# design.net
KiCad netlist of a schematic drawn in Altium Designer
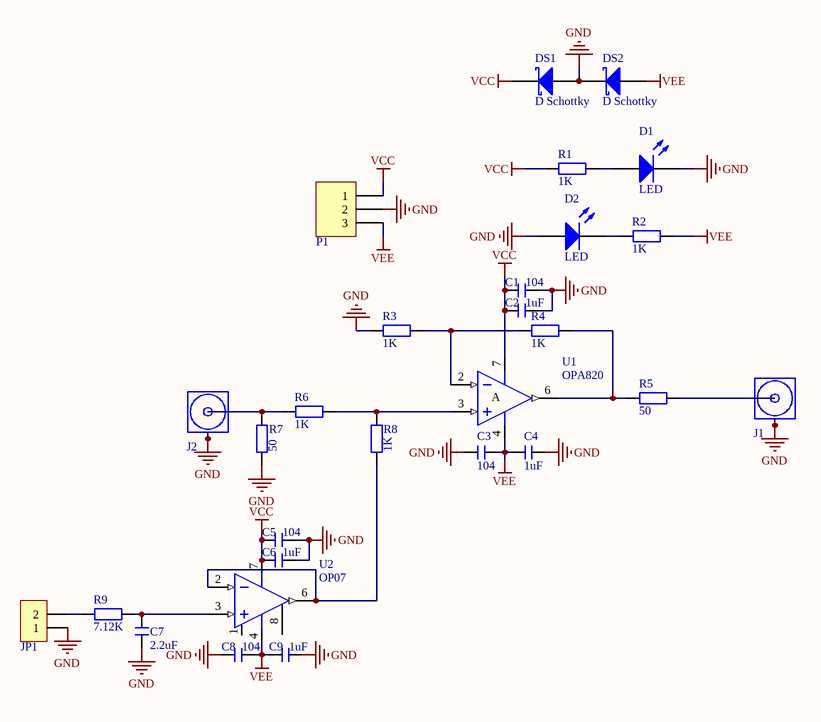
[diagram p0: 同向调偏放大器.SchDoc]

(export (version "E")
  (design (tool "Eeschema 10.0.6"))
  (components
    (comp (ref "C1")
      (value "104")
      (footprint "C 0603")
      (description "无极性贴片电容")
      (fields (field (name "版权归属") "源创客"))
      (libsource (lib "电阻-电容-电感") (part "C"))
    )
    (comp (ref "C2")
      (value "1uF")
      (footprint "C 0603")
      (description "无极性贴片电容")
      (fields (field (name "版权归属") "源创客"))
      (libsource (lib "电阻-电容-电感") (part "C"))
    )
    (comp (ref "C3")
      (value "104")
      (footprint "C 0603")
      (description "无极性贴片电容")
      (fields (field (name "版权归属") "源创客"))
      (libsource (lib "电阻-电容-电感") (part "C"))
    )
    (comp (ref "C4")
      (value "1uF")
      (footprint "C 0603")
      (description "无极性贴片电容")
      (fields (field (name "版权归属") "源创客"))
      (libsource (lib "电阻-电容-电感") (part "C"))
    )
    (comp (ref "C5")
      (value "104")
      (footprint "C 0603")
      (description "无极性贴片电容")
      (fields (field (name "版权归属") "源创客"))
      (libsource (lib "电阻-电容-电感") (part "C"))
    )
    (comp (ref "C6")
      (value "1uF")
      (footprint "C 0603")
      (description "无极性贴片电容")
      (fields (field (name "版权归属") "源创客"))
      (libsource (lib "电阻-电容-电感") (part "C"))
    )
    (comp (ref "C7")
      (value "2.2uF")
      (footprint "C 0603")
      (description "无极性贴片电容")
      (fields (field (name "版权归属") "源创客"))
      (libsource (lib "电阻-电容-电感") (part "C"))
    )
    (comp (ref "C8")
      (value "104")
      (footprint "C 0603")
      (description "无极性贴片电容")
      (fields (field (name "版权归属") "源创客"))
      (libsource (lib "电阻-电容-电感") (part "C"))
    )
    (comp (ref "C9")
      (value "1uF")
      (footprint "C 0603")
      (description "无极性贴片电容")
      (fields (field (name "版权归属") "源创客"))
      (libsource (lib "电阻-电容-电感") (part "C"))
    )
    (comp (ref "D1")
      (value "LED")
      (footprint "LED_0805")
      (description "发光二极管")
      (fields (field (name "PUBLISHER") "Altium Limited"))
      (libsource (lib "LIB") (part "LED"))
    )
    (comp (ref "D2")
      (value "LED")
      (footprint "LED_0805")
      (description "发光二极管")
      (fields (field (name "PUBLISHER") "Altium Limited"))
      (libsource (lib "LIB") (part "LED"))
    )
    (comp (ref "DS1")
      (value "D Schottky")
      (footprint "DIODE-SMA")
      (description "Schottky Diode")
      (fields (field (name "PUBLISHER") "Altium Limited"))
      (libsource (lib "LIB") (part "D Schottky"))
    )
    (comp (ref "DS2")
      (value "D Schottky")
      (footprint "DIODE-SMA")
      (description "Schottky Diode")
      (fields (field (name "PUBLISHER") "Altium Limited"))
      (libsource (lib "LIB") (part "D Schottky"))
    )
    (comp (ref "J1") (value "COAX") (footprint "MCX5.08-5-H") (libsource (lib "LIB") (part "COAX")))
    (comp (ref "J2") (value "COAX") (footprint "MCX5.08-5-H") (libsource (lib "LIB") (part "COAX")))
    (comp (ref "JP1")
      (value "HDR-1X2")
      (footprint "HDR-1X2")
      (description "2P接插件")
      (fields (field (name "版权归属") "源创客"))
      (libsource (lib "接插件") (part "Header 2"))
    )
    (comp (ref "P1")
      (value "Header 3")
      (footprint "HDR3X1_B2")
      (description "接插件")
      (fields (field (name "PUBLISHER") "Altium Limited"))
      (libsource (lib "LIB") (part "Header 3"))
    )
    (comp (ref "R1")
      (value "1K")
      (footprint "R 0805")
      (description "贴片电阻")
      (fields (field (name "版权归属") "源创客"))
      (libsource (lib "电阻-电容-电感") (part "R"))
    )
    (comp (ref "R2")
      (value "1K")
      (footprint "R 0805")
      (description "贴片电阻")
      (fields (field (name "版权归属") "源创客"))
      (libsource (lib "电阻-电容-电感") (part "R"))
    )
    (comp (ref "R3")
      (value "1K")
      (footprint "R 0603")
      (description "贴片电阻")
      (fields (field (name "版权归属") "源创客"))
      (libsource (lib "电阻-电容-电感") (part "R"))
    )
    (comp (ref "R4")
      (value "1K")
      (footprint "R 0603")
      (description "贴片电阻")
      (fields (field (name "版权归属") "源创客"))
      (libsource (lib "电阻-电容-电感") (part "R"))
    )
    (comp (ref "R5")
      (value "50")
      (footprint "R 0603")
      (description "贴片电阻")
      (fields (field (name "版权归属") "源创客"))
      (libsource (lib "电阻-电容-电感") (part "R"))
    )
    (comp (ref "R6")
      (value "1K")
      (footprint "R 0603")
      (description "贴片电阻")
      (fields (field (name "版权归属") "源创客"))
      (libsource (lib "电阻-电容-电感") (part "R"))
    )
    (comp (ref "R7")
      (value "50")
      (footprint "R 0603")
      (description "贴片电阻")
      (fields (field (name "版权归属") "源创客"))
      (libsource (lib "电阻-电容-电感") (part "R"))
    )
    (comp (ref "R8")
      (value "1K")
      (footprint "R 0603")
      (description "贴片电阻")
      (fields (field (name "版权归属") "源创客"))
      (libsource (lib "电阻-电容-电感") (part "R"))
    )
    (comp (ref "R9")
      (value "7.12K")
      (footprint "R 0603")
      (description "贴片电阻")
      (fields (field (name "版权归属") "源创客"))
      (libsource (lib "电阻-电容-电感") (part "R"))
    )
    (comp (ref "U1")
      (value "OPA820")
      (footprint "SOIC8_N")
      (description "单位增益稳定低噪声电压反馈运算放大器")
      (libsource (lib "LIB") (part "OPA820"))
    )
    (comp (ref "U2")
      (value "OP07")
      (footprint "SO8_L")
      (description "Precision Operational Amplifiers")
      (libsource (lib "LIB") (part "OP07"))
    )
  )
  (nets
    (net (code "1") (name "GND") (class "Default")
      (node (ref "C1") (pin "1") (pinfunction "1_1") (pintype "passive"))
      (node (ref "C2") (pin "1") (pinfunction "1_1") (pintype "passive"))
      (node (ref "C3") (pin "2") (pinfunction "2_2") (pintype "passive"))
      (node (ref "C4") (pin "1") (pinfunction "1_1") (pintype "passive"))
      (node (ref "C5") (pin "1") (pinfunction "1_1") (pintype "passive"))
      (node (ref "C6") (pin "1") (pinfunction "1_1") (pintype "passive"))
      (node (ref "C7") (pin "2") (pinfunction "2_2") (pintype "passive"))
      (node (ref "C8") (pin "2") (pinfunction "2_2") (pintype "passive"))
      (node (ref "C9") (pin "1") (pinfunction "1_1") (pintype "passive"))
      (node (ref "D1") (pin "2") (pinfunction "K_2") (pintype "passive"))
      (node (ref "D2") (pin "1") (pinfunction "A_1") (pintype "passive"))
      (node (ref "DS1") (pin "1") (pinfunction "1_1") (pintype "passive"))
      (node (ref "DS2") (pin "2") (pinfunction "2_2") (pintype "passive"))
      (node (ref "J1") (pin "2") (pinfunction "GND_2") (pintype "passive"))
      (node (ref "J1") (pin "3") (pinfunction "GND_3") (pintype "passive"))
      (node (ref "J1") (pin "4") (pinfunction "GND_4") (pintype "passive"))
      (node (ref "J1") (pin "5") (pinfunction "GND_5") (pintype "passive"))
      (node (ref "J2") (pin "2") (pinfunction "GND_2") (pintype "passive"))
      (node (ref "J2") (pin "3") (pinfunction "GND_3") (pintype "passive"))
      (node (ref "J2") (pin "4") (pinfunction "GND_4") (pintype "passive"))
      (node (ref "J2") (pin "5") (pinfunction "GND_5") (pintype "passive"))
      (node (ref "JP1") (pin "1") (pinfunction "1_1") (pintype "passive"))
      (node (ref "P1") (pin "2") (pinfunction "2_2") (pintype "passive"))
      (node (ref "R3") (pin "1") (pinfunction "1_1") (pintype "passive"))
      (node (ref "R7") (pin "1") (pinfunction "1_1") (pintype "passive"))
    )
    (net (code "2") (name "Net-(D1-A)") (class "Default")
      (node (ref "D1") (pin "1") (pinfunction "A_1") (pintype "passive"))
      (node (ref "R1") (pin "2") (pinfunction "2_2") (pintype "passive"))
    )
    (net (code "3") (name "Net-(D2-K)") (class "Default")
      (node (ref "D2") (pin "2") (pinfunction "K_2") (pintype "passive"))
      (node (ref "R2") (pin "1") (pinfunction "1_1") (pintype "passive"))
    )
    (net (code "4") (name "Net-(J1-Signal)") (class "Default")
      (node (ref "J1") (pin "1") (pinfunction "Signal_1") (pintype "passive"))
      (node (ref "R5") (pin "2") (pinfunction "2_2") (pintype "passive"))
    )
    (net (code "5") (name "Net-(J2-Signal)") (class "Default")
      (node (ref "J2") (pin "1") (pinfunction "Signal_1") (pintype "passive"))
      (node (ref "R6") (pin "2") (pinfunction "2_2") (pintype "passive"))
      (node (ref "R7") (pin "2") (pinfunction "2_2") (pintype "passive"))
    )
    (net (code "6") (name "Net-(JP1-Pad2)") (class "Default")
      (node (ref "JP1") (pin "2") (pinfunction "2_2") (pintype "passive"))
      (node (ref "R9") (pin "2") (pinfunction "2_2") (pintype "passive"))
    )
    (net (code "7") (name "Net-(U1-+IN)") (class "Default")
      (node (ref "R6") (pin "1") (pinfunction "1_1") (pintype "passive"))
      (node (ref "R8") (pin "2") (pinfunction "2_2") (pintype "passive"))
      (node (ref "U1") (pin "3") (pinfunction "+IN_3") (pintype "input"))
    )
    (net (code "8") (name "Net-(U1--IN)") (class "Default")
      (node (ref "R3") (pin "2") (pinfunction "2_2") (pintype "passive"))
      (node (ref "R4") (pin "1") (pinfunction "1_1") (pintype "passive"))
      (node (ref "U1") (pin "2") (pinfunction "-IN_2") (pintype "input"))
    )
    (net (code "9") (name "Net-(U1-OUT)") (class "Default")
      (node (ref "R4") (pin "2") (pinfunction "2_2") (pintype "passive"))
      (node (ref "R5") (pin "1") (pinfunction "1_1") (pintype "passive"))
      (node (ref "U1") (pin "6") (pinfunction "OUT_6") (pintype "output"))
    )
    (net (code "10") (name "Net-(U2-IN+)") (class "Default")
      (node (ref "C7") (pin "1") (pinfunction "1_1") (pintype "passive"))
      (node (ref "R9") (pin "1") (pinfunction "1_1") (pintype "passive"))
      (node (ref "U2") (pin "3") (pinfunction "IN+_3") (pintype "input"))
    )
    (net (code "11") (name "Net-(U2-IN-)") (class "Default")
      (node (ref "R8") (pin "1") (pinfunction "1_1") (pintype "passive"))
      (node (ref "U2") (pin "2") (pinfunction "IN-_2") (pintype "input"))
      (node (ref "U2") (pin "6") (pinfunction "OUT_6") (pintype "output"))
    )
    (net (code "12") (name "VCC") (class "Default")
      (node (ref "C1") (pin "2") (pinfunction "2_2") (pintype "passive"))
      (node (ref "C2") (pin "2") (pinfunction "2_2") (pintype "passive"))
      (node (ref "C5") (pin "2") (pinfunction "2_2") (pintype "passive"))
      (node (ref "C6") (pin "2") (pinfunction "2_2") (pintype "passive"))
      (node (ref "DS1") (pin "2") (pinfunction "2_2") (pintype "passive"))
      (node (ref "P1") (pin "1") (pinfunction "1_1") (pintype "passive"))
      (node (ref "R1") (pin "1") (pinfunction "1_1") (pintype "passive"))
      (node (ref "U1") (pin "7") (pinfunction "V+_7") (pintype "power_in"))
      (node (ref "U2") (pin "7") (pinfunction "V+_7") (pintype "power_in"))
    )
    (net (code "13") (name "VEE") (class "Default")
      (node (ref "C3") (pin "1") (pinfunction "1_1") (pintype "passive"))
      (node (ref "C4") (pin "2") (pinfunction "2_2") (pintype "passive"))
      (node (ref "C8") (pin "1") (pinfunction "1_1") (pintype "passive"))
      (node (ref "C9") (pin "2") (pinfunction "2_2") (pintype "passive"))
      (node (ref "DS2") (pin "1") (pinfunction "1_1") (pintype "passive"))
      (node (ref "P1") (pin "3") (pinfunction "3_3") (pintype "passive"))
      (node (ref "R2") (pin "2") (pinfunction "2_2") (pintype "passive"))
      (node (ref "U1") (pin "4") (pinfunction "V-_4") (pintype "power_in"))
      (node (ref "U2") (pin "4") (pinfunction "V-_4") (pintype "power_in"))
    )
    (net (code "14") (name "unconnected-(U2-OFFSET_N1-Pad1)") (class "Default")
      (node (ref "U2") (pin "1") (pinfunction "OFFSET_N1_1") (pintype "passive"))
    )
    (net (code "15") (name "unconnected-(U2-OFFSET_N2-Pad8)") (class "Default")
      (node (ref "U2") (pin "8") (pinfunction "OFFSET_N2_8") (pintype "passive"))
    )
  )
)
